# amp_test_arm_qfp.net
KiCad netlist of a schematic drawn in EAGLE
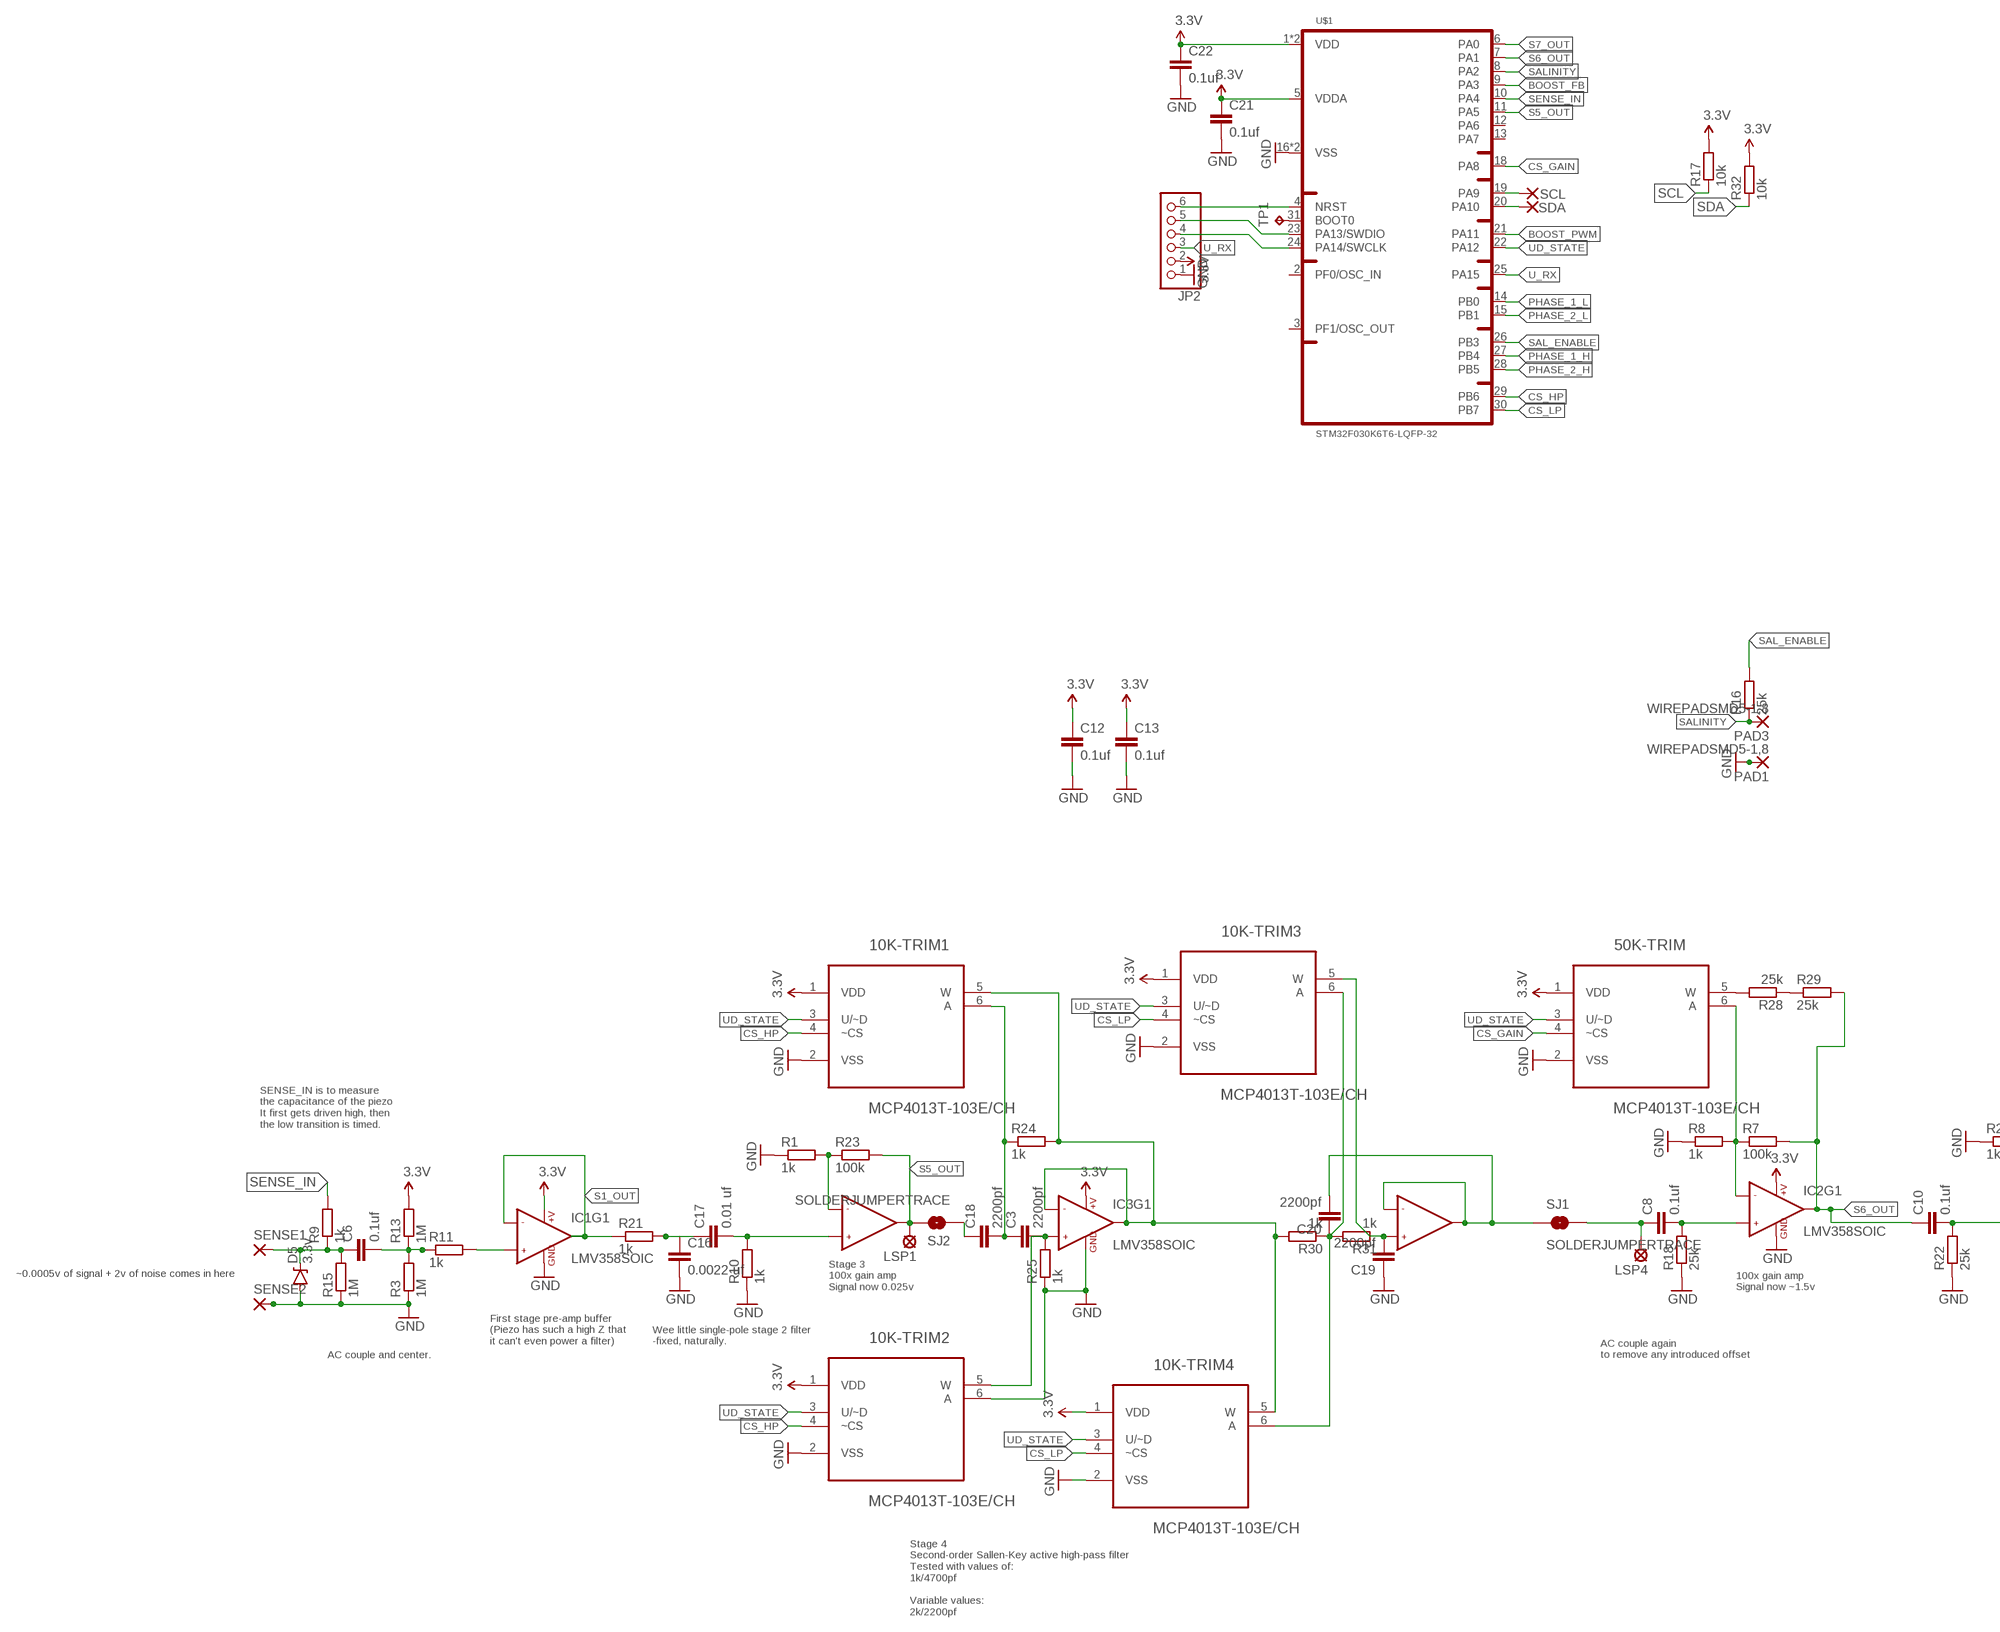
[diagram p0: schematic, sheet 1, part 1 of 2]
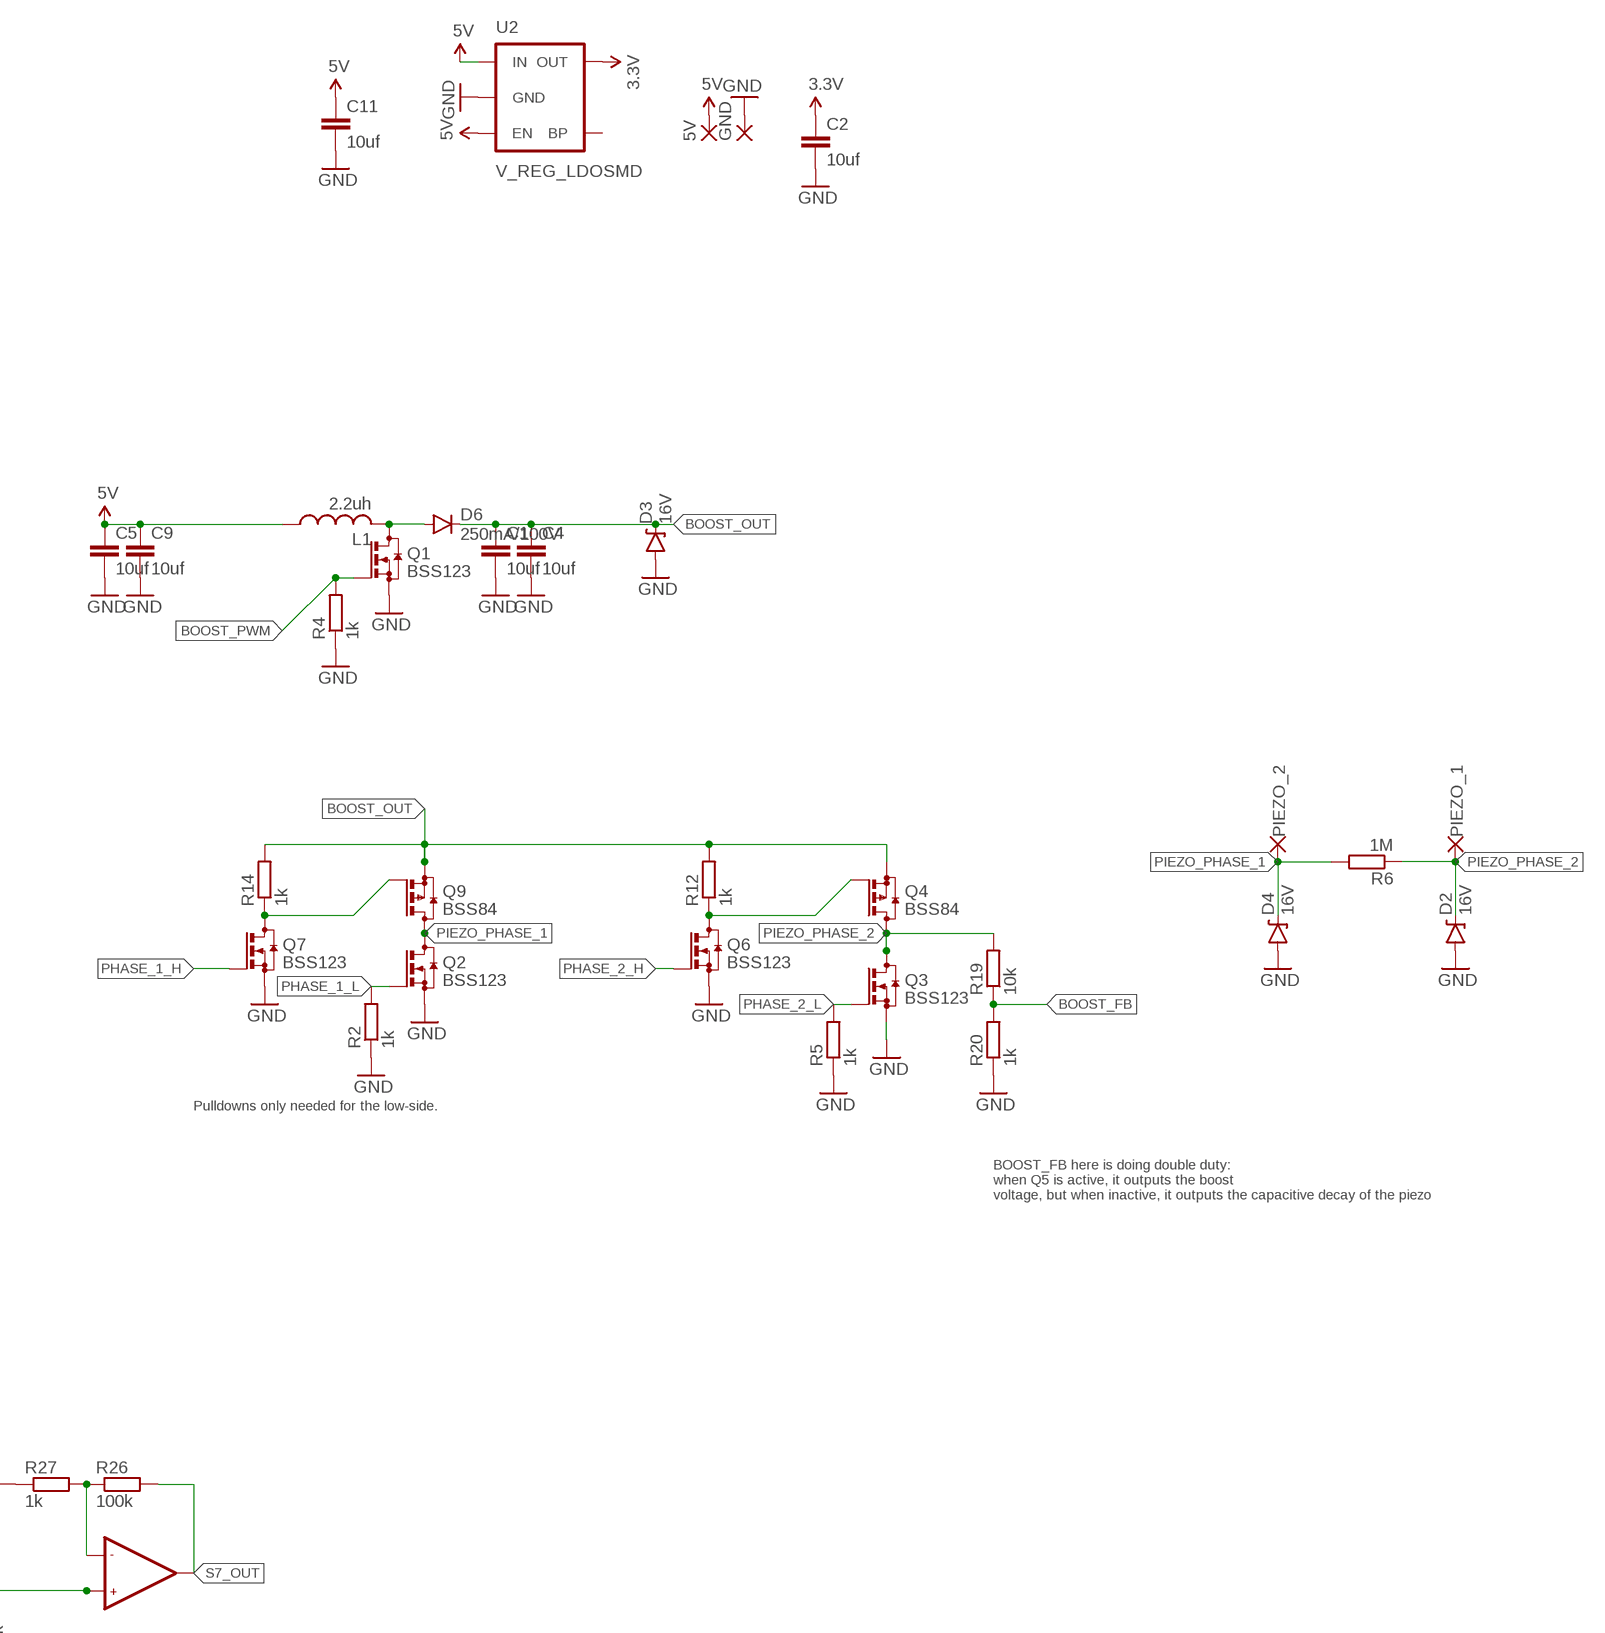
[diagram p1: schematic, sheet 1, part 2 of 2]

(export (version "E")
  (design (tool "Eeschema 10.0.6"))
  (components
    (comp (ref "5V")
      (value "SMD5")
      (footprint "eagle-import:SMD2,54-5,08")
      (libsource (lib "eagle-import") (part "SMD5"))
    )
    (comp (ref "10K-TRIM1")
      (value "MCP4013T-103E/CH")
      (footprint "eagle-import:SOT95P280X145-6N")
      (fields (field (name "DIGI-KEY_PART_NUMBER") "MCP4013T-103E/CHCT-ND") (field (name "MF") "Microchip"))
      (libsource (lib "eagle-import") (part "MCP4013T-103E/CH"))
    )
    (comp (ref "10K-TRIM2")
      (value "MCP4013T-103E/CH")
      (footprint "eagle-import:SOT95P280X145-6N")
      (fields (field (name "DIGI-KEY_PART_NUMBER") "MCP4013T-103E/CHCT-ND") (field (name "MF") "Microchip"))
      (libsource (lib "eagle-import") (part "MCP4013T-103E/CH"))
    )
    (comp (ref "10K-TRIM3")
      (value "MCP4013T-103E/CH")
      (footprint "eagle-import:SOT95P280X145-6N")
      (fields (field (name "DIGI-KEY_PART_NUMBER") "MCP4013T-103E/CHCT-ND") (field (name "MF") "Microchip"))
      (libsource (lib "eagle-import") (part "MCP4013T-103E/CH"))
    )
    (comp (ref "10K-TRIM4")
      (value "MCP4013T-103E/CH")
      (footprint "eagle-import:SOT95P280X145-6N")
      (fields (field (name "DIGI-KEY_PART_NUMBER") "MCP4013T-103E/CHCT-ND") (field (name "MF") "Microchip"))
      (libsource (lib "eagle-import") (part "MCP4013T-103E/CH"))
    )
    (comp (ref "50K-TRIM")
      (value "MCP4013T-103E/CH")
      (footprint "eagle-import:SOT95P280X145-6N")
      (fields (field (name "DIGI-KEY_PART_NUMBER") "MCP4013T-103E/CHCT-ND") (field (name "MF") "Microchip"))
      (libsource (lib "eagle-import") (part "MCP4013T-103E/CH"))
    )
    (comp (ref "C1")
      (value "10uf")
      (footprint "eagle-import:C0805")
      (libsource (lib "eagle-import") (part "C-EUC0805"))
    )
    (comp (ref "C2")
      (value "10uf")
      (footprint "eagle-import:C0603")
      (libsource (lib "eagle-import") (part "C-EUC0603"))
    )
    (comp (ref "C3")
      (value "2200pf")
      (footprint "eagle-import:C0603")
      (libsource (lib "eagle-import") (part "C-EUC0603"))
    )
    (comp (ref "C4")
      (value "10uf")
      (footprint "eagle-import:C0805")
      (libsource (lib "eagle-import") (part "C-EUC0805"))
    )
    (comp (ref "C5")
      (value "10uf")
      (footprint "eagle-import:C0603")
      (libsource (lib "eagle-import") (part "C-EUC0603"))
    )
    (comp (ref "C6")
      (value "0.1uf")
      (footprint "eagle-import:C0603")
      (libsource (lib "eagle-import") (part "C-EUC0603"))
    )
    (comp (ref "C8")
      (value "0.1uf")
      (footprint "eagle-import:C0603")
      (libsource (lib "eagle-import") (part "C-EUC0603"))
    )
    (comp (ref "C9")
      (value "10uf")
      (footprint "eagle-import:C0603")
      (libsource (lib "eagle-import") (part "C-EUC0603"))
    )
    (comp (ref "C10")
      (value "0.1uf")
      (footprint "eagle-import:C0603")
      (libsource (lib "eagle-import") (part "C-EUC0603"))
    )
    (comp (ref "C11")
      (value "10uf")
      (footprint "eagle-import:C0603")
      (libsource (lib "eagle-import") (part "C-EUC0603"))
    )
    (comp (ref "C12")
      (value "0.1uf")
      (footprint "eagle-import:C0603")
      (libsource (lib "eagle-import") (part "C-EUC0603"))
    )
    (comp (ref "C13")
      (value "0.1uf")
      (footprint "eagle-import:C0603")
      (libsource (lib "eagle-import") (part "C-EUC0603"))
    )
    (comp (ref "C16")
      (value "0.0022 uf")
      (footprint "eagle-import:C0603")
      (libsource (lib "eagle-import") (part "C-EUC0603"))
    )
    (comp (ref "C17")
      (value "0.01 uf")
      (footprint "eagle-import:C0603")
      (libsource (lib "eagle-import") (part "C-EUC0603"))
    )
    (comp (ref "C18")
      (value "2200pf")
      (footprint "eagle-import:C0603")
      (libsource (lib "eagle-import") (part "C-EUC0603"))
    )
    (comp (ref "C19")
      (value "2200pf")
      (footprint "eagle-import:C0603")
      (libsource (lib "eagle-import") (part "C-EUC0603"))
    )
    (comp (ref "C20")
      (value "2200pf")
      (footprint "eagle-import:C0603")
      (libsource (lib "eagle-import") (part "C-EUC0603"))
    )
    (comp (ref "C21")
      (value "0.1uf")
      (footprint "eagle-import:C0603")
      (libsource (lib "eagle-import") (part "C-EUC0603"))
    )
    (comp (ref "C22")
      (value "0.1uf")
      (footprint "eagle-import:C0603")
      (libsource (lib "eagle-import") (part "C-EUC0603"))
    )
    (comp (ref "D2")
      (value "16V")
      (footprint "eagle-import:SOD-323")
      (libsource (lib "eagle-import") (part "DIODE-ZENER3.3V"))
    )
    (comp (ref "D3")
      (value "16V")
      (footprint "eagle-import:SOD-323")
      (libsource (lib "eagle-import") (part "DIODE-ZENER3.3V"))
    )
    (comp (ref "D4")
      (value "16V")
      (footprint "eagle-import:SOD-323")
      (libsource (lib "eagle-import") (part "DIODE-ZENER3.3V"))
    )
    (comp (ref "D5")
      (value "3.3v")
      (footprint "eagle-import:SOD-323")
      (libsource (lib "eagle-import") (part "DIODE-ZENER3.3V"))
    )
    (comp (ref "D6")
      (value "250mA/100V")
      (footprint "eagle-import:SOD-323")
      (libsource (lib "eagle-import") (part "DIODEBAS16"))
    )
    (comp (ref "GND")
      (value "SMD5")
      (footprint "eagle-import:SMD2,54-5,08")
      (libsource (lib "eagle-import") (part "SMD5"))
    )
    (comp (ref "IC1")
      (value "LMV358SOIC")
      (footprint "eagle-import:SO08")
      (libsource (lib "eagle-import") (part "LMV358SOIC"))
    )
    (comp (ref "IC2")
      (value "LMV358SOIC")
      (footprint "eagle-import:SO08")
      (libsource (lib "eagle-import") (part "LMV358SOIC"))
    )
    (comp (ref "IC3")
      (value "LMV358SOIC")
      (footprint "eagle-import:SO08")
      (libsource (lib "eagle-import") (part "LMV358SOIC"))
    )
    (comp (ref "JP2")
      (value "PINHD-1X6")
      (footprint "eagle-import:1X06")
      (libsource (lib "eagle-import") (part "PINHD-1X6"))
    )
    (comp (ref "L1")
      (value "2.2uh")
      (footprint "eagle-import:L2825P")
      (libsource (lib "eagle-import") (part "L-USL2825P"))
    )
    (comp (ref "LSP1")
      (value "LSP10")
      (footprint "eagle-import:LSP10")
      (libsource (lib "eagle-import") (part "LSP10"))
    )
    (comp (ref "LSP4")
      (value "LSP10")
      (footprint "eagle-import:LSP10")
      (libsource (lib "eagle-import") (part "LSP10"))
    )
    (comp (ref "PAD1")
      (value "WIREPADSMD5-1,8")
      (footprint "eagle-import:5-1,8")
      (libsource (lib "eagle-import") (part "WIREPADSMD5-1,8"))
    )
    (comp (ref "PAD3")
      (value "WIREPADSMD5-1,8")
      (footprint "eagle-import:5-1,8")
      (libsource (lib "eagle-import") (part "WIREPADSMD5-1,8"))
    )
    (comp (ref "PIEZO_1")
      (value "SMD5")
      (footprint "eagle-import:SMD2,54-5,08")
      (libsource (lib "eagle-import") (part "SMD5"))
    )
    (comp (ref "PIEZO_2")
      (value "SMD5")
      (footprint "eagle-import:SMD2,54-5,08")
      (libsource (lib "eagle-import") (part "SMD5"))
    )
    (comp (ref "Q1")
      (value "BSS123")
      (footprint "eagle-import:SOT23")
      (libsource (lib "eagle-import") (part "BSS123"))
    )
    (comp (ref "Q2")
      (value "BSS123")
      (footprint "eagle-import:SOT23")
      (libsource (lib "eagle-import") (part "BSS123"))
    )
    (comp (ref "Q3")
      (value "BSS123")
      (footprint "eagle-import:SOT23")
      (libsource (lib "eagle-import") (part "BSS123"))
    )
    (comp (ref "Q4")
      (value "BSS84")
      (footprint "eagle-import:SOT23")
      (libsource (lib "eagle-import") (part "BSS84"))
    )
    (comp (ref "Q6")
      (value "BSS123")
      (footprint "eagle-import:SOT23")
      (libsource (lib "eagle-import") (part "BSS123"))
    )
    (comp (ref "Q7")
      (value "BSS123")
      (footprint "eagle-import:SOT23")
      (libsource (lib "eagle-import") (part "BSS123"))
    )
    (comp (ref "Q9")
      (value "BSS84")
      (footprint "eagle-import:SOT23")
      (libsource (lib "eagle-import") (part "BSS84"))
    )
    (comp (ref "R1")
      (value "1k")
      (footprint "eagle-import:R0603")
      (libsource (lib "eagle-import") (part "R-EU_R0603"))
    )
    (comp (ref "R2")
      (value "1k")
      (footprint "eagle-import:R0603")
      (libsource (lib "eagle-import") (part "R-EU_R0603"))
    )
    (comp (ref "R3")
      (value "1M")
      (footprint "eagle-import:R0603")
      (libsource (lib "eagle-import") (part "R-EU_R0603"))
    )
    (comp (ref "R4")
      (value "1k")
      (footprint "eagle-import:R0603")
      (libsource (lib "eagle-import") (part "R-EU_R0603"))
    )
    (comp (ref "R5")
      (value "1k")
      (footprint "eagle-import:R0603")
      (libsource (lib "eagle-import") (part "R-EU_R0603"))
    )
    (comp (ref "R6")
      (value "1M")
      (footprint "eagle-import:R0603")
      (libsource (lib "eagle-import") (part "R-EU_R0603"))
    )
    (comp (ref "R7")
      (value "100k")
      (footprint "eagle-import:R0603")
      (libsource (lib "eagle-import") (part "R-EU_R0603"))
    )
    (comp (ref "R8")
      (value "1k")
      (footprint "eagle-import:R0603")
      (libsource (lib "eagle-import") (part "R-EU_R0603"))
    )
    (comp (ref "R9")
      (value "1k")
      (footprint "eagle-import:R0603")
      (libsource (lib "eagle-import") (part "R-EU_R0603"))
    )
    (comp (ref "R10")
      (value "1k")
      (footprint "eagle-import:R0603")
      (libsource (lib "eagle-import") (part "R-EU_R0603"))
    )
    (comp (ref "R11")
      (value "1k")
      (footprint "eagle-import:R0603")
      (libsource (lib "eagle-import") (part "R-EU_R0603"))
    )
    (comp (ref "R12")
      (value "1k")
      (footprint "eagle-import:R0603")
      (libsource (lib "eagle-import") (part "R-EU_R0603"))
    )
    (comp (ref "R13")
      (value "1M")
      (footprint "eagle-import:R0603")
      (libsource (lib "eagle-import") (part "R-EU_R0603"))
    )
    (comp (ref "R14")
      (value "1k")
      (footprint "eagle-import:R0603")
      (libsource (lib "eagle-import") (part "R-EU_R0603"))
    )
    (comp (ref "R15")
      (value "1M")
      (footprint "eagle-import:R0603")
      (libsource (lib "eagle-import") (part "R-EU_R0603"))
    )
    (comp (ref "R16")
      (value "25k")
      (footprint "eagle-import:R0603")
      (libsource (lib "eagle-import") (part "R-EU_R0603"))
    )
    (comp (ref "R17")
      (value "10k")
      (footprint "eagle-import:R0603")
      (libsource (lib "eagle-import") (part "R-EU_R0603"))
    )
    (comp (ref "R18")
      (value "25k")
      (footprint "eagle-import:R0603")
      (libsource (lib "eagle-import") (part "R-EU_R0603"))
    )
    (comp (ref "R19")
      (value "10k")
      (footprint "eagle-import:R0603")
      (libsource (lib "eagle-import") (part "R-EU_R0603"))
    )
    (comp (ref "R20")
      (value "1k")
      (footprint "eagle-import:R0603")
      (libsource (lib "eagle-import") (part "R-EU_R0603"))
    )
    (comp (ref "R21")
      (value "1k")
      (footprint "eagle-import:R0603")
      (libsource (lib "eagle-import") (part "R-EU_R0603"))
    )
    (comp (ref "R22")
      (value "25k")
      (footprint "eagle-import:R0603")
      (libsource (lib "eagle-import") (part "R-EU_R0603"))
    )
    (comp (ref "R23")
      (value "100k")
      (footprint "eagle-import:R0603")
      (libsource (lib "eagle-import") (part "R-EU_R0603"))
    )
    (comp (ref "R24")
      (value "1k")
      (footprint "eagle-import:R0603")
      (libsource (lib "eagle-import") (part "R-EU_R0603"))
    )
    (comp (ref "R25")
      (value "1k")
      (footprint "eagle-import:R0603")
      (libsource (lib "eagle-import") (part "R-EU_R0603"))
    )
    (comp (ref "R26")
      (value "100k")
      (footprint "eagle-import:R0603")
      (libsource (lib "eagle-import") (part "R-EU_R0603"))
    )
    (comp (ref "R27")
      (value "1k")
      (footprint "eagle-import:R0603")
      (libsource (lib "eagle-import") (part "R-EU_R0603"))
    )
    (comp (ref "R28")
      (value "25k")
      (footprint "eagle-import:R0603")
      (libsource (lib "eagle-import") (part "R-EU_R0603"))
    )
    (comp (ref "R29")
      (value "25k")
      (footprint "eagle-import:R0603")
      (libsource (lib "eagle-import") (part "R-EU_R0603"))
    )
    (comp (ref "R30")
      (value "1k")
      (footprint "eagle-import:R0603")
      (libsource (lib "eagle-import") (part "R-EU_R0603"))
    )
    (comp (ref "R31")
      (value "1k")
      (footprint "eagle-import:R0603")
      (libsource (lib "eagle-import") (part "R-EU_R0603"))
    )
    (comp (ref "R32")
      (value "10k")
      (footprint "eagle-import:R0603")
      (libsource (lib "eagle-import") (part "R-EU_R0603"))
    )
    (comp (ref "SCL")
      (value "SMD5")
      (footprint "eagle-import:SMD2,54-5,08")
      (libsource (lib "eagle-import") (part "SMD5"))
    )
    (comp (ref "SDA")
      (value "SMD5")
      (footprint "eagle-import:SMD2,54-5,08")
      (libsource (lib "eagle-import") (part "SMD5"))
    )
    (comp (ref "SENSE1")
      (value "SMD5")
      (footprint "eagle-import:SMD2,54-5,08")
      (libsource (lib "eagle-import") (part "SMD5"))
    )
    (comp (ref "SENSE2")
      (value "SMD5")
      (footprint "eagle-import:SMD2,54-5,08")
      (libsource (lib "eagle-import") (part "SMD5"))
    )
    (comp (ref "SJ1")
      (value "SOLDERJUMPERTRACE")
      (footprint "eagle-import:SJ_2S-TRACE")
      (libsource (lib "eagle-import") (part "SOLDERJUMPERTRACE"))
    )
    (comp (ref "SJ2")
      (value "SOLDERJUMPERTRACE")
      (footprint "eagle-import:SJ_2S-TRACE")
      (libsource (lib "eagle-import") (part "SOLDERJUMPERTRACE"))
    )
    (comp (ref "TP1")
      (value "TPTP12R")
      (footprint "eagle-import:TP12R")
      (libsource (lib "eagle-import") (part "TPTP12R"))
    )
    (comp (ref "U$1")
      (value "STM32F030K6T6-LQFP-32")
      (footprint "eagle-import:LQFP-32")
      (libsource (lib "eagle-import") (part "STM32F030K6T6-LQFP-32"))
    )
    (comp (ref "U2")
      (value "V_REG_LDOSMD")
      (footprint "eagle-import:SOT23-5")
      (libsource (lib "eagle-import") (part "V_REG_LDOSMD"))
    )
  )
  (nets
    (net (code "1") (name "3.3V") (class "Default")
      (node (ref "10K-TRIM1") (pin "1") (pinfunction "VDD_1") (pintype "power_in"))
      (node (ref "10K-TRIM2") (pin "1") (pinfunction "VDD_1") (pintype "power_in"))
      (node (ref "10K-TRIM3") (pin "1") (pinfunction "VDD_1") (pintype "power_in"))
      (node (ref "10K-TRIM4") (pin "1") (pinfunction "VDD_1") (pintype "power_in"))
      (node (ref "50K-TRIM") (pin "1") (pinfunction "VDD_1") (pintype "power_in"))
      (node (ref "C12") (pin "1") (pinfunction "1_1") (pintype "passive"))
      (node (ref "C13") (pin "1") (pinfunction "1_1") (pintype "passive"))
      (node (ref "C2") (pin "1") (pinfunction "1_1") (pintype "passive"))
      (node (ref "C21") (pin "1") (pinfunction "1_1") (pintype "passive"))
      (node (ref "C22") (pin "1") (pinfunction "1_1") (pintype "passive"))
      (node (ref "IC1") (pin "8") (pinfunction "+V_8") (pintype "power_in"))
      (node (ref "IC2") (pin "8") (pinfunction "+V_8") (pintype "power_in"))
      (node (ref "IC3") (pin "8") (pinfunction "+V_8") (pintype "power_in"))
      (node (ref "JP2") (pin "2") (pinfunction "2_2") (pintype "passive"))
      (node (ref "R13") (pin "2") (pinfunction "2_2") (pintype "passive"))
      (node (ref "R17") (pin "2") (pinfunction "2_2") (pintype "passive"))
      (node (ref "R32") (pin "2") (pinfunction "2_2") (pintype "passive"))
      (node (ref "U$1") (pin "1") (pinfunction "VDD_1") (pintype "bidirectional"))
      (node (ref "U$1") (pin "17") (pinfunction "VDD_17") (pintype "bidirectional"))
      (node (ref "U$1") (pin "5") (pinfunction "VDDA_5") (pintype "bidirectional"))
      (node (ref "U2") (pin "5") (pinfunction "OUT_5") (pintype "passive"))
    )
    (net (code "2") (name "5V") (class "Default")
      (node (ref "5V") (pin "1") (pinfunction "P_1") (pintype "passive"))
      (node (ref "C11") (pin "1") (pinfunction "1_1") (pintype "passive"))
      (node (ref "C5") (pin "1") (pinfunction "1_1") (pintype "passive"))
      (node (ref "C9") (pin "1") (pinfunction "1_1") (pintype "passive"))
      (node (ref "L1") (pin "1") (pinfunction "1_1") (pintype "passive"))
      (node (ref "U2") (pin "1") (pinfunction "IN_1") (pintype "input"))
      (node (ref "U2") (pin "3") (pinfunction "EN_3") (pintype "input"))
    )
    (net (code "3") (name "BOOST_FB") (class "Default")
      (node (ref "R19") (pin "1") (pinfunction "1_1") (pintype "passive"))
      (node (ref "R20") (pin "2") (pinfunction "2_2") (pintype "passive"))
      (node (ref "U$1") (pin "9") (pinfunction "PA3_9") (pintype "bidirectional"))
    )
    (net (code "4") (name "BOOST_OUT") (class "Default")
      (node (ref "C1") (pin "1") (pinfunction "1_1") (pintype "passive"))
      (node (ref "C4") (pin "1") (pinfunction "1_1") (pintype "passive"))
      (node (ref "D3") (pin "C") (pinfunction "C_C") (pintype "passive"))
      (node (ref "D6") (pin "C") (pinfunction "C_C") (pintype "passive"))
      (node (ref "Q4") (pin "2") (pinfunction "S_2") (pintype "passive"))
      (node (ref "Q9") (pin "2") (pinfunction "S_2") (pintype "passive"))
      (node (ref "R12") (pin "2") (pinfunction "2_2") (pintype "passive"))
      (node (ref "R14") (pin "2") (pinfunction "2_2") (pintype "passive"))
    )
    (net (code "5") (name "BOOST_PWM") (class "Default")
      (node (ref "Q1") (pin "1") (pinfunction "G_1") (pintype "passive"))
      (node (ref "R4") (pin "2") (pinfunction "2_2") (pintype "passive"))
      (node (ref "U$1") (pin "21") (pinfunction "PA11_21") (pintype "bidirectional"))
    )
    (net (code "6") (name "CS_GAIN") (class "Default")
      (node (ref "50K-TRIM") (pin "4") (pinfunction "~{CS}_4") (pintype "input"))
      (node (ref "U$1") (pin "18") (pinfunction "PA8_18") (pintype "bidirectional"))
    )
    (net (code "7") (name "CS_HP") (class "Default")
      (node (ref "10K-TRIM1") (pin "4") (pinfunction "~{CS}_4") (pintype "input"))
      (node (ref "10K-TRIM2") (pin "4") (pinfunction "~{CS}_4") (pintype "input"))
      (node (ref "U$1") (pin "29") (pinfunction "PB6_29") (pintype "bidirectional"))
    )
    (net (code "8") (name "CS_LP") (class "Default")
      (node (ref "10K-TRIM3") (pin "4") (pinfunction "~{CS}_4") (pintype "input"))
      (node (ref "10K-TRIM4") (pin "4") (pinfunction "~{CS}_4") (pintype "input"))
      (node (ref "U$1") (pin "30") (pinfunction "PB7_30") (pintype "bidirectional"))
    )
    (net (code "9") (name "GND") (class "Default")
      (node (ref "10K-TRIM1") (pin "2") (pinfunction "VSS_2") (pintype "power_in"))
      (node (ref "10K-TRIM2") (pin "2") (pinfunction "VSS_2") (pintype "power_in"))
      (node (ref "10K-TRIM2") (pin "6") (pinfunction "A_6") (pintype "passive"))
      (node (ref "10K-TRIM3") (pin "2") (pinfunction "VSS_2") (pintype "power_in"))
      (node (ref "10K-TRIM4") (pin "2") (pinfunction "VSS_2") (pintype "power_in"))
      (node (ref "50K-TRIM") (pin "2") (pinfunction "VSS_2") (pintype "power_in"))
      (node (ref "C1") (pin "2") (pinfunction "2_2") (pintype "passive"))
      (node (ref "C11") (pin "2") (pinfunction "2_2") (pintype "passive"))
      (node (ref "C12") (pin "2") (pinfunction "2_2") (pintype "passive"))
      (node (ref "C13") (pin "2") (pinfunction "2_2") (pintype "passive"))
      (node (ref "C16") (pin "2") (pinfunction "2_2") (pintype "passive"))
      (node (ref "C19") (pin "1") (pinfunction "1_1") (pintype "passive"))
      (node (ref "C2") (pin "2") (pinfunction "2_2") (pintype "passive"))
      (node (ref "C21") (pin "2") (pinfunction "2_2") (pintype "passive"))
      (node (ref "C22") (pin "2") (pinfunction "2_2") (pintype "passive"))
      (node (ref "C4") (pin "2") (pinfunction "2_2") (pintype "passive"))
      (node (ref "C5") (pin "2") (pinfunction "2_2") (pintype "passive"))
      (node (ref "C9") (pin "2") (pinfunction "2_2") (pintype "passive"))
      (node (ref "D2") (pin "A") (pinfunction "A_A") (pintype "passive"))
      (node (ref "D3") (pin "A") (pinfunction "A_A") (pintype "passive"))
      (node (ref "D4") (pin "A") (pinfunction "A_A") (pintype "passive"))
      (node (ref "D5") (pin "A") (pinfunction "A_A") (pintype "passive"))
      (node (ref "GND") (pin "1") (pinfunction "P_1") (pintype "passive"))
      (node (ref "IC1") (pin "4") (pinfunction "GND_4") (pintype "power_in"))
      (node (ref "IC2") (pin "4") (pinfunction "GND_4") (pintype "power_in"))
      (node (ref "IC3") (pin "4") (pinfunction "GND_4") (pintype "power_in"))
      (node (ref "JP2") (pin "1") (pinfunction "1_1") (pintype "passive"))
      (node (ref "PAD1") (pin "1") (pinfunction "P_1") (pintype "passive"))
      (node (ref "Q1") (pin "2") (pinfunction "S_2") (pintype "passive"))
      (node (ref "Q2") (pin "2") (pinfunction "S_2") (pintype "passive"))
      (node (ref "Q3") (pin "2") (pinfunction "S_2") (pintype "passive"))
      (node (ref "Q6") (pin "2") (pinfunction "S_2") (pintype "passive"))
      (node (ref "Q7") (pin "2") (pinfunction "S_2") (pintype "passive"))
      (node (ref "R1") (pin "1") (pinfunction "1_1") (pintype "passive"))
      (node (ref "R10") (pin "1") (pinfunction "1_1") (pintype "passive"))
      (node (ref "R15") (pin "1") (pinfunction "1_1") (pintype "passive"))
      (node (ref "R18") (pin "1") (pinfunction "1_1") (pintype "passive"))
      (node (ref "R2") (pin "1") (pinfunction "1_1") (pintype "passive"))
      (node (ref "R20") (pin "1") (pinfunction "1_1") (pintype "passive"))
      (node (ref "R22") (pin "1") (pinfunction "1_1") (pintype "passive"))
      (node (ref "R25") (pin "1") (pinfunction "1_1") (pintype "passive"))
      (node (ref "R27") (pin "1") (pinfunction "1_1") (pintype "passive"))
      (node (ref "R3") (pin "1") (pinfunction "1_1") (pintype "passive"))
      (node (ref "R4") (pin "1") (pinfunction "1_1") (pintype "passive"))
      (node (ref "R5") (pin "1") (pinfunction "1_1") (pintype "passive"))
      (node (ref "R8") (pin "1") (pinfunction "1_1") (pintype "passive"))
      (node (ref "SENSE2") (pin "1") (pinfunction "P_1") (pintype "passive"))
      (node (ref "U$1") (pin "16") (pinfunction "VSS_16") (pintype "bidirectional"))
      (node (ref "U$1") (pin "32") (pinfunction "VSS_32") (pintype "bidirectional"))
      (node (ref "U2") (pin "2") (pinfunction "GND_2") (pintype "input"))
    )
    (net (code "10") (name "Net-(10K-TRIM1-A)") (class "Default")
      (node (ref "10K-TRIM1") (pin "6") (pinfunction "A_6") (pintype "passive"))
      (node (ref "C18") (pin "2") (pinfunction "2_2") (pintype "passive"))
      (node (ref "C3") (pin "1") (pinfunction "1_1") (pintype "passive"))
      (node (ref "R24") (pin "1") (pinfunction "1_1") (pintype "passive"))
    )
    (net (code "11") (name "Net-(10K-TRIM1-W)") (class "Default")
      (node (ref "10K-TRIM1") (pin "5") (pinfunction "W_5") (pintype "passive"))
      (node (ref "10K-TRIM4") (pin "5") (pinfunction "W_5") (pintype "passive"))
      (node (ref "IC3") (pin "1") (pinfunction "OUT1_1") (pintype "output"))
      (node (ref "IC3") (pin "2") (pinfunction "-IN1_2") (pintype "input"))
      (node (ref "R24") (pin "2") (pinfunction "2_2") (pintype "passive"))
      (node (ref "R30") (pin "2") (pinfunction "2_2") (pintype "passive"))
    )
    (net (code "12") (name "Net-(10K-TRIM2-W)") (class "Default")
      (node (ref "10K-TRIM2") (pin "5") (pinfunction "W_5") (pintype "passive"))
      (node (ref "C3") (pin "2") (pinfunction "2_2") (pintype "passive"))
      (node (ref "IC3") (pin "3") (pinfunction "+IN1_3") (pintype "input"))
      (node (ref "R25") (pin "2") (pinfunction "2_2") (pintype "passive"))
    )
    (net (code "13") (name "Net-(10K-TRIM3-A)") (class "Default")
      (node (ref "10K-TRIM3") (pin "6") (pinfunction "A_6") (pintype "passive"))
      (node (ref "10K-TRIM4") (pin "6") (pinfunction "A_6") (pintype "passive"))
      (node (ref "C20") (pin "1") (pinfunction "1_1") (pintype "passive"))
      (node (ref "R30") (pin "1") (pinfunction "1_1") (pintype "passive"))
      (node (ref "R31") (pin "2") (pinfunction "2_2") (pintype "passive"))
    )
    (net (code "14") (name "Net-(10K-TRIM3-W)") (class "Default")
      (node (ref "10K-TRIM3") (pin "5") (pinfunction "W_5") (pintype "passive"))
      (node (ref "C19") (pin "2") (pinfunction "2_2") (pintype "passive"))
      (node (ref "IC3") (pin "5") (pinfunction "+IN2_5") (pintype "input"))
      (node (ref "R31") (pin "1") (pinfunction "1_1") (pintype "passive"))
    )
    (net (code "15") (name "Net-(50K-TRIM-A)") (class "Default")
      (node (ref "50K-TRIM") (pin "6") (pinfunction "A_6") (pintype "passive"))
      (node (ref "IC2") (pin "2") (pinfunction "-IN1_2") (pintype "input"))
      (node (ref "R7") (pin "1") (pinfunction "1_1") (pintype "passive"))
      (node (ref "R8") (pin "2") (pinfunction "2_2") (pintype "passive"))
    )
    (net (code "16") (name "Net-(50K-TRIM-W)") (class "Default")
      (node (ref "50K-TRIM") (pin "5") (pinfunction "W_5") (pintype "passive"))
      (node (ref "R28") (pin "2") (pinfunction "2_2") (pintype "passive"))
    )
    (net (code "17") (name "Net-(C6-Pad2)") (class "Default")
      (node (ref "C6") (pin "2") (pinfunction "2_2") (pintype "passive"))
      (node (ref "R11") (pin "1") (pinfunction "1_1") (pintype "passive"))
      (node (ref "R13") (pin "1") (pinfunction "1_1") (pintype "passive"))
      (node (ref "R3") (pin "2") (pinfunction "2_2") (pintype "passive"))
    )
    (net (code "18") (name "Net-(C8-Pad1)") (class "Default")
      (node (ref "C8") (pin "1") (pinfunction "1_1") (pintype "passive"))
      (node (ref "LSP4") (pin "MP") (pinfunction "MP_MP") (pintype "passive"))
      (node (ref "SJ1") (pin "2") (pinfunction "2_2") (pintype "passive"))
    )
    (net (code "19") (name "Net-(C16-Pad1)") (class "Default")
      (node (ref "C16") (pin "1") (pinfunction "1_1") (pintype "passive"))
      (node (ref "C17") (pin "1") (pinfunction "1_1") (pintype "passive"))
      (node (ref "R21") (pin "2") (pinfunction "2_2") (pintype "passive"))
    )
    (net (code "20") (name "Net-(C18-Pad1)") (class "Default")
      (node (ref "C18") (pin "1") (pinfunction "1_1") (pintype "passive"))
      (node (ref "SJ2") (pin "1") (pinfunction "1_1") (pintype "passive"))
    )
    (net (code "21") (name "Net-(IC1A-+IN1)") (class "Default")
      (node (ref "IC1") (pin "3") (pinfunction "+IN1_3") (pintype "input"))
      (node (ref "R11") (pin "2") (pinfunction "2_2") (pintype "passive"))
    )
    (net (code "22") (name "Net-(IC1B-+IN2)") (class "Default")
      (node (ref "C17") (pin "2") (pinfunction "2_2") (pintype "passive"))
      (node (ref "IC1") (pin "5") (pinfunction "+IN2_5") (pintype "input"))
      (node (ref "R10") (pin "2") (pinfunction "2_2") (pintype "passive"))
    )
    (net (code "23") (name "Net-(IC1B--IN2)") (class "Default")
      (node (ref "IC1") (pin "6") (pinfunction "-IN2_6") (pintype "input"))
      (node (ref "R1") (pin "2") (pinfunction "2_2") (pintype "passive"))
      (node (ref "R23") (pin "1") (pinfunction "1_1") (pintype "passive"))
    )
    (net (code "24") (name "Net-(IC2A-+IN1)") (class "Default")
      (node (ref "C8") (pin "2") (pinfunction "2_2") (pintype "passive"))
      (node (ref "IC2") (pin "3") (pinfunction "+IN1_3") (pintype "input"))
      (node (ref "R18") (pin "2") (pinfunction "2_2") (pintype "passive"))
    )
    (net (code "25") (name "Net-(IC2B-+IN2)") (class "Default")
      (node (ref "C10") (pin "2") (pinfunction "2_2") (pintype "passive"))
      (node (ref "IC2") (pin "5") (pinfunction "+IN2_5") (pintype "input"))
      (node (ref "R22") (pin "2") (pinfunction "2_2") (pintype "passive"))
    )
    (net (code "26") (name "Net-(IC2B--IN2)") (class "Default")
      (node (ref "IC2") (pin "6") (pinfunction "-IN2_6") (pintype "input"))
      (node (ref "R26") (pin "1") (pinfunction "1_1") (pintype "passive"))
      (node (ref "R27") (pin "2") (pinfunction "2_2") (pintype "passive"))
    )
    (net (code "27") (name "Net-(IC3B--IN2)") (class "Default")
      (node (ref "C20") (pin "2") (pinfunction "2_2") (pintype "passive"))
      (node (ref "IC3") (pin "6") (pinfunction "-IN2_6") (pintype "input"))
      (node (ref "IC3") (pin "7") (pinfunction "OUT2_7") (pintype "output"))
      (node (ref "SJ1") (pin "1") (pinfunction "1_1") (pintype "passive"))
    )
    (net (code "28") (name "Net-(Q1-D)") (class "Default")
      (node (ref "D6") (pin "A") (pinfunction "A_A") (pintype "passive"))
      (node (ref "L1") (pin "2") (pinfunction "2_2") (pintype "passive"))
      (node (ref "Q1") (pin "3") (pinfunction "D_3") (pintype "passive"))
    )
    (net (code "29") (name "Net-(Q4-G)") (class "Default")
      (node (ref "Q4") (pin "1") (pinfunction "G_1") (pintype "passive"))
      (node (ref "Q6") (pin "3") (pinfunction "D_3") (pintype "passive"))
      (node (ref "R12") (pin "1") (pinfunction "1_1") (pintype "passive"))
    )
    (net (code "30") (name "Net-(Q7-D)") (class "Default")
      (node (ref "Q7") (pin "3") (pinfunction "D_3") (pintype "passive"))
      (node (ref "Q9") (pin "1") (pinfunction "G_1") (pintype "passive"))
      (node (ref "R14") (pin "1") (pinfunction "1_1") (pintype "passive"))
    )
    (net (code "31") (name "Net-(R28-Pad1)") (class "Default")
      (node (ref "R28") (pin "1") (pinfunction "1_1") (pintype "passive"))
      (node (ref "R29") (pin "1") (pinfunction "1_1") (pintype "passive"))
    )
    (net (code "32") (name "Net-(SENSE1-P)") (class "Default")
      (node (ref "C6") (pin "1") (pinfunction "1_1") (pintype "passive"))
      (node (ref "D5") (pin "C") (pinfunction "C_C") (pintype "passive"))
      (node (ref "R15") (pin "2") (pinfunction "2_2") (pintype "passive"))
      (node (ref "R9") (pin "1") (pinfunction "1_1") (pintype "passive"))
      (node (ref "SENSE1") (pin "1") (pinfunction "P_1") (pintype "passive"))
    )
    (net (code "33") (name "Net-(U$1-BOOT0)") (class "Default")
      (node (ref "TP1") (pin "TP") (pinfunction "TP_TP") (pintype "input"))
      (node (ref "U$1") (pin "31") (pinfunction "BOOT0_31") (pintype "bidirectional"))
    )
    (net (code "34") (name "Net-(U$1-NRST)") (class "Default")
      (node (ref "JP2") (pin "6") (pinfunction "6_6") (pintype "passive"))
      (node (ref "U$1") (pin "4") (pinfunction "NRST_4") (pintype "bidirectional"))
    )
    (net (code "35") (name "Net-(U$1-PA13{slash}SWDIO)") (class "Default")
      (node (ref "JP2") (pin "5") (pinfunction "5_5") (pintype "passive"))
      (node (ref "U$1") (pin "23") (pinfunction "PA13/SWDIO_23") (pintype "bidirectional"))
    )
    (net (code "36") (name "Net-(U$1-PA14{slash}SWCLK)") (class "Default")
      (node (ref "JP2") (pin "4") (pinfunction "4_4") (pintype "passive"))
      (node (ref "U$1") (pin "24") (pinfunction "PA14/SWCLK_24") (pintype "bidirectional"))
    )
    (net (code "37") (name "PHASE_1_H") (class "Default")
      (node (ref "Q7") (pin "1") (pinfunction "G_1") (pintype "passive"))
      (node (ref "U$1") (pin "27") (pinfunction "PB4_27") (pintype "bidirectional"))
    )
    (net (code "38") (name "PHASE_1_L") (class "Default")
      (node (ref "Q2") (pin "1") (pinfunction "G_1") (pintype "passive"))
      (node (ref "R2") (pin "2") (pinfunction "2_2") (pintype "passive"))
      (node (ref "U$1") (pin "14") (pinfunction "PB0_14") (pintype "bidirectional"))
    )
    (net (code "39") (name "PHASE_2_H") (class "Default")
      (node (ref "Q6") (pin "1") (pinfunction "G_1") (pintype "passive"))
      (node (ref "U$1") (pin "28") (pinfunction "PB5_28") (pintype "bidirectional"))
    )
    (net (code "40") (name "PHASE_2_L") (class "Default")
      (node (ref "Q3") (pin "1") (pinfunction "G_1") (pintype "passive"))
      (node (ref "R5") (pin "2") (pinfunction "2_2") (pintype "passive"))
      (node (ref "U$1") (pin "15") (pinfunction "PB1_15") (pintype "bidirectional"))
    )
    (net (code "41") (name "PIEZO_PHASE_1") (class "Default")
      (node (ref "D4") (pin "C") (pinfunction "C_C") (pintype "passive"))
      (node (ref "PIEZO_2") (pin "1") (pinfunction "P_1") (pintype "passive"))
      (node (ref "Q2") (pin "3") (pinfunction "D_3") (pintype "passive"))
      (node (ref "Q9") (pin "3") (pinfunction "D_3") (pintype "passive"))
      (node (ref "R6") (pin "2") (pinfunction "2_2") (pintype "passive"))
    )
    (net (code "42") (name "PIEZO_PHASE_2") (class "Default")
      (node (ref "D2") (pin "C") (pinfunction "C_C") (pintype "passive"))
      (node (ref "PIEZO_1") (pin "1") (pinfunction "P_1") (pintype "passive"))
      (node (ref "Q3") (pin "3") (pinfunction "D_3") (pintype "passive"))
      (node (ref "Q4") (pin "3") (pinfunction "D_3") (pintype "passive"))
      (node (ref "R19") (pin "2") (pinfunction "2_2") (pintype "passive"))
      (node (ref "R6") (pin "1") (pinfunction "1_1") (pintype "passive"))
    )
    (net (code "43") (name "S1_OUT") (class "Default")
      (node (ref "IC1") (pin "1") (pinfunction "OUT1_1") (pintype "output"))
      (node (ref "IC1") (pin "2") (pinfunction "-IN1_2") (pintype "input"))
      (node (ref "R21") (pin "1") (pinfunction "1_1") (pintype "passive"))
    )
    (net (code "44") (name "S5_OUT") (class "Default")
      (node (ref "IC1") (pin "7") (pinfunction "OUT2_7") (pintype "output"))
      (node (ref "LSP1") (pin "MP") (pinfunction "MP_MP") (pintype "passive"))
      (node (ref "R23") (pin "2") (pinfunction "2_2") (pintype "passive"))
      (node (ref "SJ2") (pin "2") (pinfunction "2_2") (pintype "passive"))
      (node (ref "U$1") (pin "11") (pinfunction "PA5_11") (pintype "bidirectional"))
    )
    (net (code "45") (name "S6_OUT") (class "Default")
      (node (ref "C10") (pin "1") (pinfunction "1_1") (pintype "passive"))
      (node (ref "IC2") (pin "1") (pinfunction "OUT1_1") (pintype "output"))
      (node (ref "R29") (pin "2") (pinfunction "2_2") (pintype "passive"))
      (node (ref "R7") (pin "2") (pinfunction "2_2") (pintype "passive"))
      (node (ref "U$1") (pin "7") (pinfunction "PA1_7") (pintype "bidirectional"))
    )
    (net (code "46") (name "S7_OUT") (class "Default")
      (node (ref "IC2") (pin "7") (pinfunction "OUT2_7") (pintype "output"))
      (node (ref "R26") (pin "2") (pinfunction "2_2") (pintype "passive"))
      (node (ref "U$1") (pin "6") (pinfunction "PA0_6") (pintype "bidirectional"))
    )
    (net (code "47") (name "SALINITY") (class "Default")
      (node (ref "PAD3") (pin "1") (pinfunction "P_1") (pintype "passive"))
      (node (ref "R16") (pin "1") (pinfunction "1_1") (pintype "passive"))
      (node (ref "U$1") (pin "8") (pinfunction "PA2_8") (pintype "bidirectional"))
    )
    (net (code "48") (name "SAL_ENABLE") (class "Default")
      (node (ref "R16") (pin "2") (pinfunction "2_2") (pintype "passive"))
      (node (ref "U$1") (pin "26") (pinfunction "PB3_26") (pintype "bidirectional"))
    )
    (net (code "49") (name "SCL") (class "Default")
      (node (ref "R17") (pin "1") (pinfunction "1_1") (pintype "passive"))
      (node (ref "SCL") (pin "1") (pinfunction "P_1") (pintype "passive"))
      (node (ref "U$1") (pin "19") (pinfunction "PA9_19") (pintype "bidirectional"))
    )
    (net (code "50") (name "SDA") (class "Default")
      (node (ref "R32") (pin "1") (pinfunction "1_1") (pintype "passive"))
      (node (ref "SDA") (pin "1") (pinfunction "P_1") (pintype "passive"))
      (node (ref "U$1") (pin "20") (pinfunction "PA10_20") (pintype "bidirectional"))
    )
    (net (code "51") (name "SENSE_IN") (class "Default")
      (node (ref "R9") (pin "2") (pinfunction "2_2") (pintype "passive"))
      (node (ref "U$1") (pin "10") (pinfunction "PA4_10") (pintype "bidirectional"))
    )
    (net (code "52") (name "UD_STATE") (class "Default")
      (node (ref "10K-TRIM1") (pin "3") (pinfunction "U/~{D}_3") (pintype "input"))
      (node (ref "10K-TRIM2") (pin "3") (pinfunction "U/~{D}_3") (pintype "input"))
      (node (ref "10K-TRIM3") (pin "3") (pinfunction "U/~{D}_3") (pintype "input"))
      (node (ref "10K-TRIM4") (pin "3") (pinfunction "U/~{D}_3") (pintype "input"))
      (node (ref "50K-TRIM") (pin "3") (pinfunction "U/~{D}_3") (pintype "input"))
      (node (ref "U$1") (pin "22") (pinfunction "PA12_22") (pintype "bidirectional"))
    )
    (net (code "53") (name "U_RX") (class "Default")
      (node (ref "JP2") (pin "3") (pinfunction "3_3") (pintype "passive"))
      (node (ref "U$1") (pin "25") (pinfunction "PA15_25") (pintype "bidirectional"))
    )
    (net (code "54") (name "unconnected-(U$1-PA6-Pad12)") (class "Default")
      (node (ref "U$1") (pin "12") (pinfunction "PA6_12") (pintype "bidirectional"))
    )
    (net (code "55") (name "unconnected-(U$1-PA7-Pad13)") (class "Default")
      (node (ref "U$1") (pin "13") (pinfunction "PA7_13") (pintype "bidirectional"))
    )
    (net (code "56") (name "unconnected-(U$1-PF0{slash}OSC_IN-Pad2)") (class "Default")
      (node (ref "U$1") (pin "2") (pinfunction "PF0/OSC_IN_2") (pintype "bidirectional"))
    )
    (net (code "57") (name "unconnected-(U$1-PF1{slash}OSC_OUT-Pad3)") (class "Default")
      (node (ref "U$1") (pin "3") (pinfunction "PF1/OSC_OUT_3") (pintype "bidirectional"))
    )
    (net (code "58") (name "unconnected-(U2-BP-Pad4)") (class "Default")
      (node (ref "U2") (pin "4") (pinfunction "BP_4") (pintype "input"))
    )
  )
)
